# STM32F05.net
KiCad netlist of a schematic drawn in EAGLE
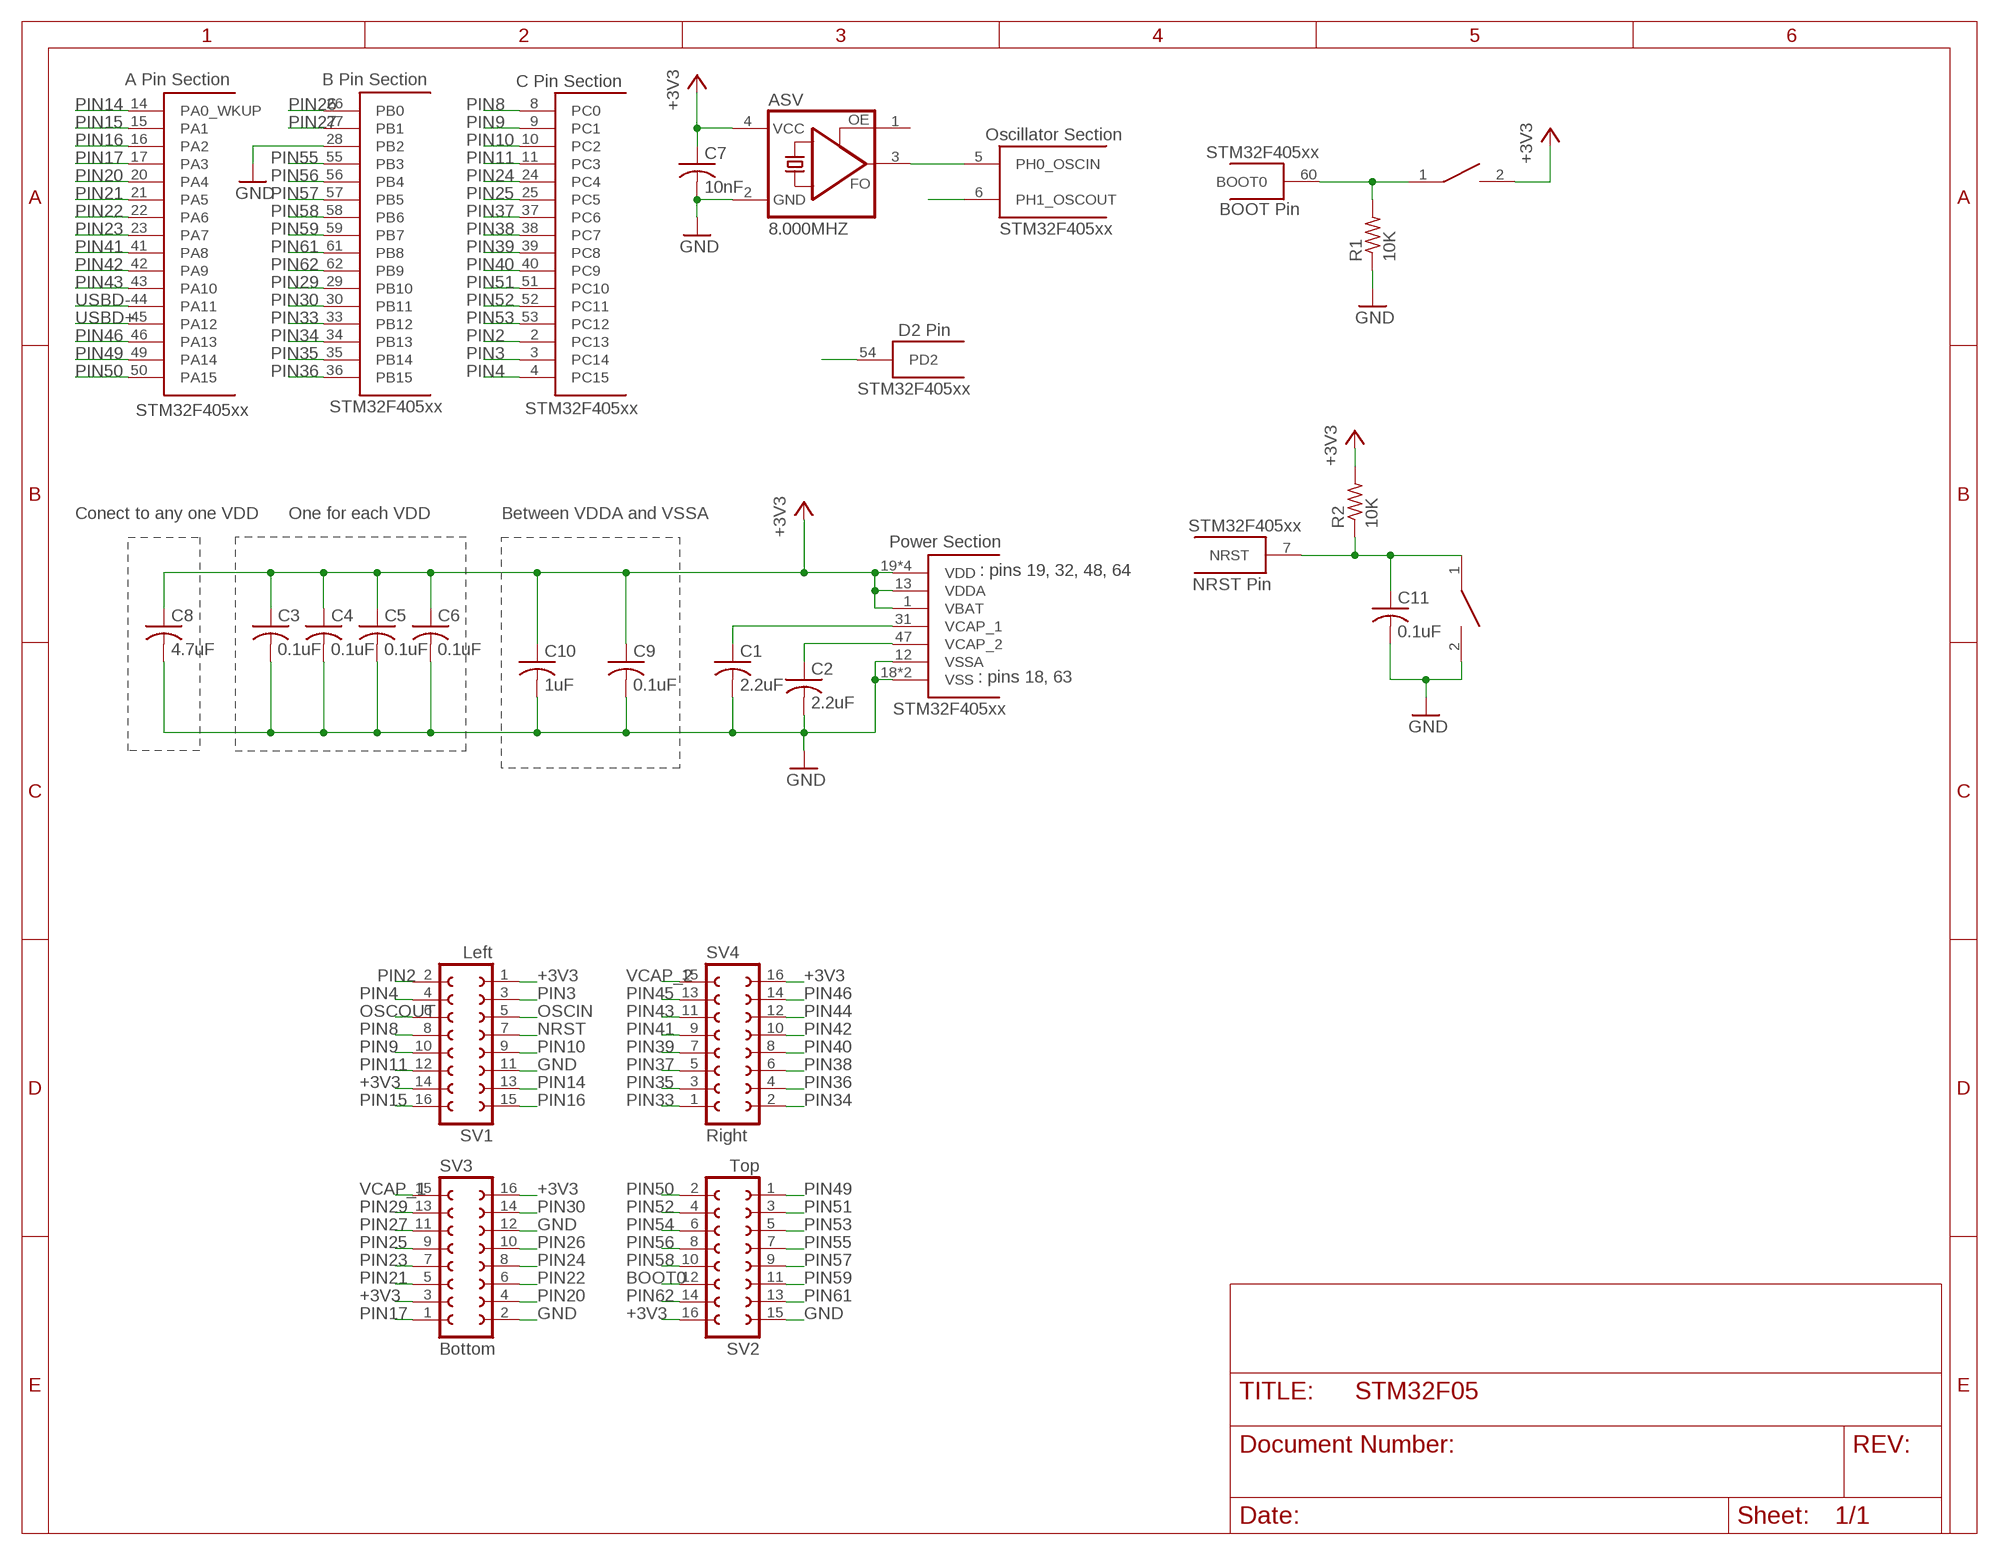
[diagram p0: schematic, sheet 1, part 1 of 2]
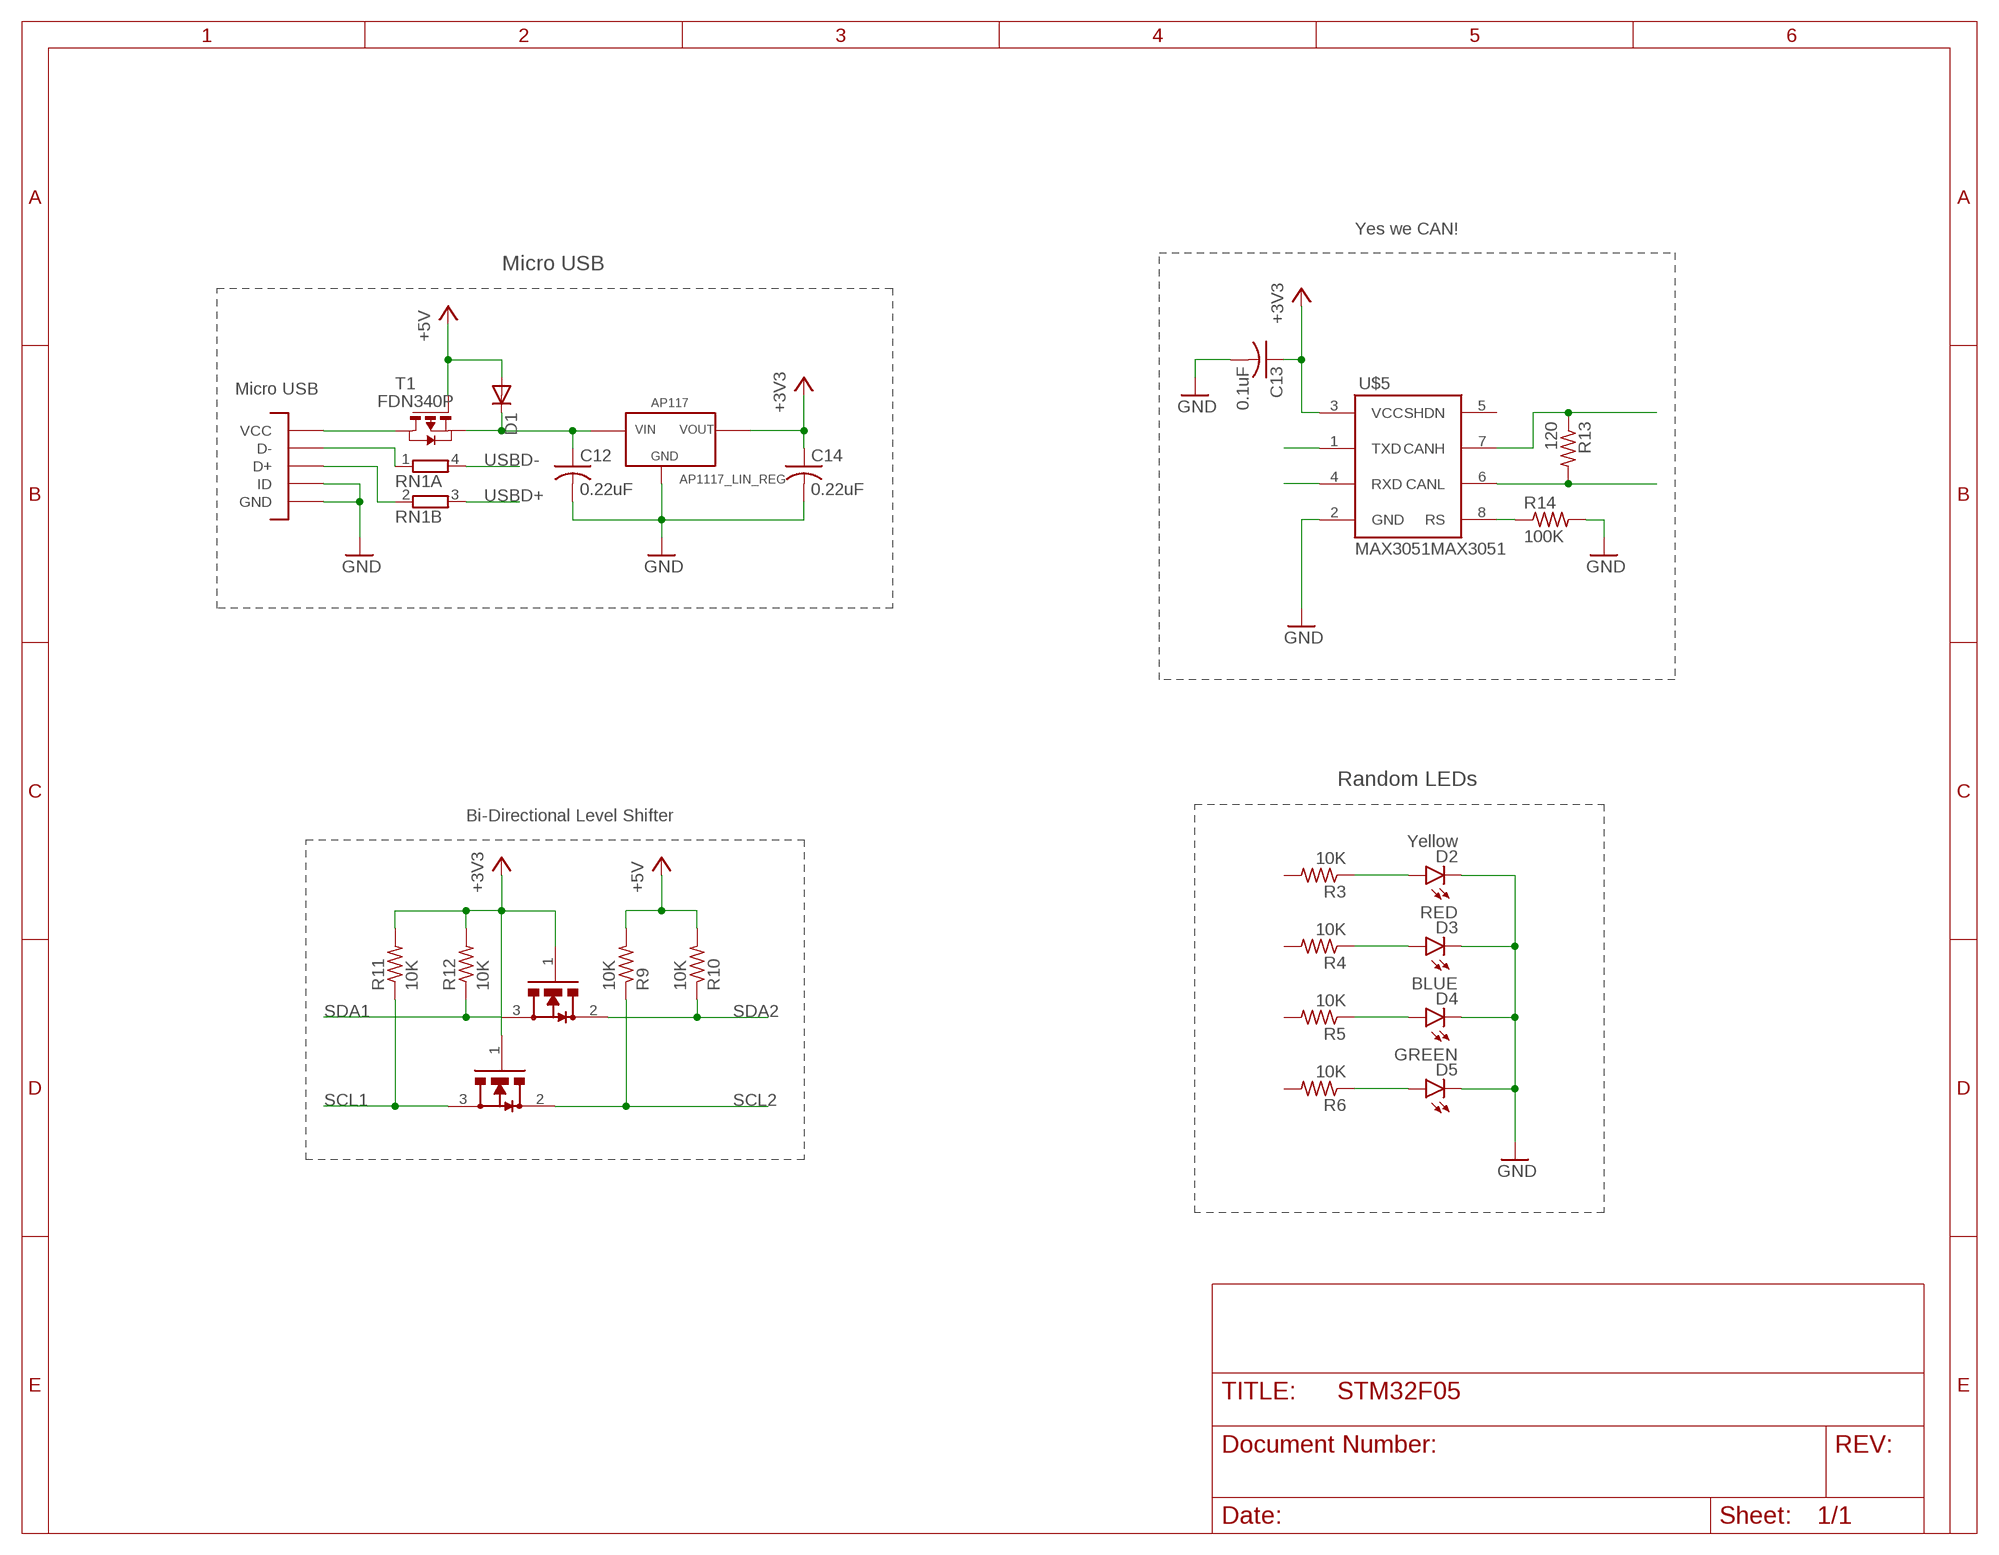
[diagram p1: schematic, sheet 1, part 2 of 2]

(export (version "E")
  (design (tool "Eeschema 10.0.6"))
  (components
    (comp (ref "ASV")
      (value "8.000MHZ")
      (footprint "eagle-import:ASF")
      (libsource (lib "eagle-import") (part "ASF"))
    )
    (comp (ref "BSS138")
      (value "n-chanel mosfet")
      (footprint "eagle-import:SOT-23-BSS138")
      (libsource (lib "eagle-import") (part "BSS138"))
    )
    (comp (ref "C1")
      (value "2.2uF")
      (footprint "eagle-import:C0603")
      (libsource (lib "eagle-import") (part "C-USC0603"))
    )
    (comp (ref "C2")
      (value "2.2uF")
      (footprint "eagle-import:C0603")
      (libsource (lib "eagle-import") (part "C-USC0603"))
    )
    (comp (ref "C3")
      (value "0.1uF")
      (footprint "eagle-import:C0603")
      (libsource (lib "eagle-import") (part "C-USC0603"))
    )
    (comp (ref "C4")
      (value "0.1uF")
      (footprint "eagle-import:C0603")
      (libsource (lib "eagle-import") (part "C-USC0603"))
    )
    (comp (ref "C5")
      (value "0.1uF")
      (footprint "eagle-import:C0603")
      (libsource (lib "eagle-import") (part "C-USC0603"))
    )
    (comp (ref "C6")
      (value "0.1uF")
      (footprint "eagle-import:C0603")
      (libsource (lib "eagle-import") (part "C-USC0603"))
    )
    (comp (ref "C7")
      (value "10nF")
      (footprint "eagle-import:C0603")
      (libsource (lib "eagle-import") (part "C-USC0603"))
    )
    (comp (ref "C8")
      (value "4.7uF")
      (footprint "eagle-import:C0603")
      (libsource (lib "eagle-import") (part "C-USC0603"))
    )
    (comp (ref "C9")
      (value "0.1uF")
      (footprint "eagle-import:C0603")
      (libsource (lib "eagle-import") (part "C-USC0603"))
    )
    (comp (ref "C10")
      (value "1uF")
      (footprint "eagle-import:C0603")
      (libsource (lib "eagle-import") (part "C-USC0603"))
    )
    (comp (ref "C11")
      (value "0.1uF")
      (footprint "eagle-import:C0603")
      (libsource (lib "eagle-import") (part "C-USC0603"))
    )
    (comp (ref "C12")
      (value "0.22uF")
      (footprint "eagle-import:C0603")
      (libsource (lib "eagle-import") (part "C-USC0603"))
    )
    (comp (ref "C13")
      (value "0.1uF")
      (footprint "eagle-import:C0603")
      (libsource (lib "eagle-import") (part "C-USC0603"))
    )
    (comp (ref "C14")
      (value "0.22uF")
      (footprint "eagle-import:C0603")
      (libsource (lib "eagle-import") (part "C-USC0603"))
    )
    (comp (ref "D1")
      (value "DIODE-DO-214AC")
      (footprint "eagle-import:DO-214AC")
      (libsource (lib "eagle-import") (part "DIODE-DO-214AC"))
    )
    (comp (ref "D2")
      (value "Yellow")
      (footprint "eagle-import:LED-0603")
      (libsource (lib "eagle-import") (part "LED-YELLOW0603"))
    )
    (comp (ref "D3")
      (value "RED")
      (footprint "eagle-import:LED-0603")
      (libsource (lib "eagle-import") (part "LED-RED0603"))
    )
    (comp (ref "D4")
      (value "BLUE")
      (footprint "eagle-import:LED-0603")
      (libsource (lib "eagle-import") (part "LED-BLUE0603"))
    )
    (comp (ref "D5")
      (value "GREEN")
      (footprint "eagle-import:LED-0603")
      (libsource (lib "eagle-import") (part "LED-GREEN0603"))
    )
    (comp (ref "R1")
      (value "10K")
      (footprint "eagle-import:R0603")
      (libsource (lib "eagle-import") (part "R-US_R0603"))
    )
    (comp (ref "R2")
      (value "10K")
      (footprint "eagle-import:R0603")
      (libsource (lib "eagle-import") (part "R-US_R0603"))
    )
    (comp (ref "R3")
      (value "10K")
      (footprint "eagle-import:R0603")
      (libsource (lib "eagle-import") (part "R-US_R0603"))
    )
    (comp (ref "R4")
      (value "10K")
      (footprint "eagle-import:R0603")
      (libsource (lib "eagle-import") (part "R-US_R0603"))
    )
    (comp (ref "R5")
      (value "10K")
      (footprint "eagle-import:R0603")
      (libsource (lib "eagle-import") (part "R-US_R0603"))
    )
    (comp (ref "R6")
      (value "10K")
      (footprint "eagle-import:R0603")
      (libsource (lib "eagle-import") (part "R-US_R0603"))
    )
    (comp (ref "R9")
      (value "10K")
      (footprint "eagle-import:R0603")
      (libsource (lib "eagle-import") (part "R-US_R0603"))
    )
    (comp (ref "R10")
      (value "10K")
      (footprint "eagle-import:R0603")
      (libsource (lib "eagle-import") (part "R-US_R0603"))
    )
    (comp (ref "R11")
      (value "10K")
      (footprint "eagle-import:R0603")
      (libsource (lib "eagle-import") (part "R-US_R0603"))
    )
    (comp (ref "R12")
      (value "10K")
      (footprint "eagle-import:R0603")
      (libsource (lib "eagle-import") (part "R-US_R0603"))
    )
    (comp (ref "R13")
      (value "120")
      (footprint "eagle-import:R0603")
      (libsource (lib "eagle-import") (part "R-US_R0603"))
    )
    (comp (ref "R14")
      (value "100K")
      (footprint "eagle-import:R0603")
      (libsource (lib "eagle-import") (part "R-US_R0603"))
    )
    (comp (ref "RN1")
      (value "2R-NEXBV4V")
      (footprint "eagle-import:EXBV4V")
      (fields (field (name "MF") "Rohm Semiconductor") (field (name "MPN") "MNR12ERAPJ220"))
      (libsource (lib "eagle-import") (part "2R-NEXBV4V"))
    )
    (comp (ref "SV1")
      (value "Left")
      (footprint "eagle-import:FE08-2")
      (libsource (lib "eagle-import") (part "FE08-2"))
    )
    (comp (ref "SV2")
      (value "Top")
      (footprint "eagle-import:FE08-2")
      (libsource (lib "eagle-import") (part "FE08-2"))
    )
    (comp (ref "SV3")
      (value "Bottom")
      (footprint "eagle-import:FE08-2")
      (libsource (lib "eagle-import") (part "FE08-2"))
    )
    (comp (ref "SV4")
      (value "Right")
      (footprint "eagle-import:FE08-2")
      (libsource (lib "eagle-import") (part "FE08-2"))
    )
    (comp (ref "T1")
      (value "FDN340P")
      (footprint "eagle-import:SOT-23")
      (libsource (lib "eagle-import") (part "FDN340P"))
    )
    (comp (ref "T2")
      (value "AP1117_LIN_REG")
      (footprint "eagle-import:SOT223")
      (libsource (lib "eagle-import") (part "AP1117_LIN_REG"))
    )
    (comp (ref "U$1")
      (value "STM32F405")
      (footprint "eagle-import:LQFP64")
      (libsource (lib "eagle-import") (part "STM32F405"))
    )
    (comp (ref "U$2")
      (value "SWITCH")
      (footprint "eagle-import:SW_2512")
      (libsource (lib "eagle-import") (part "SWITCH"))
    )
    (comp (ref "U$3")
      (value "SWITCH")
      (footprint "eagle-import:SW_2512")
      (libsource (lib "eagle-import") (part "SWITCH"))
    )
    (comp (ref "U$4")
      (value "MICROUSB")
      (footprint "eagle-import:MICRO_B")
      (libsource (lib "eagle-import") (part "MICROUSB"))
    )
    (comp (ref "U$5")
      (value "MAX3051MAX3051")
      (footprint "eagle-import:SOT23-8L")
      (libsource (lib "eagle-import") (part "MAX3051MAX3051"))
    )
    (comp (ref "U$6")
      (value "BSS138")
      (footprint "eagle-import:SOT-23-BSS138")
      (libsource (lib "eagle-import") (part "BSS138"))
    )
  )
  (nets
    (net (code "1") (name "+3V3") (class "Default")
      (node (ref "ASV") (pin "4") (pinfunction "VCC_4") (pintype "power_in"))
      (node (ref "BSS138") (pin "1") (pinfunction "G_1") (pintype "bidirectional"))
      (node (ref "C10") (pin "1") (pinfunction "1_1") (pintype "passive"))
      (node (ref "C13") (pin "1") (pinfunction "1_1") (pintype "passive"))
      (node (ref "C14") (pin "1") (pinfunction "1_1") (pintype "passive"))
      (node (ref "C3") (pin "1") (pinfunction "1_1") (pintype "passive"))
      (node (ref "C4") (pin "1") (pinfunction "1_1") (pintype "passive"))
      (node (ref "C5") (pin "1") (pinfunction "1_1") (pintype "passive"))
      (node (ref "C6") (pin "1") (pinfunction "1_1") (pintype "passive"))
      (node (ref "C7") (pin "1") (pinfunction "1_1") (pintype "passive"))
      (node (ref "C8") (pin "1") (pinfunction "1_1") (pintype "passive"))
      (node (ref "C9") (pin "1") (pinfunction "1_1") (pintype "passive"))
      (node (ref "R11") (pin "2") (pinfunction "2_2") (pintype "passive"))
      (node (ref "R12") (pin "2") (pinfunction "2_2") (pintype "passive"))
      (node (ref "R2") (pin "2") (pinfunction "2_2") (pintype "passive"))
      (node (ref "SV1") (pin "1") (pinfunction "1_1") (pintype "passive"))
      (node (ref "SV1") (pin "14") (pinfunction "14_14") (pintype "passive"))
      (node (ref "SV2") (pin "16") (pinfunction "16_16") (pintype "passive"))
      (node (ref "SV3") (pin "16") (pinfunction "16_16") (pintype "passive"))
      (node (ref "SV3") (pin "3") (pinfunction "3_3") (pintype "passive"))
      (node (ref "SV4") (pin "16") (pinfunction "16_16") (pintype "passive"))
      (node (ref "T2") (pin "TAB") (pinfunction "VOUT_TAB") (pintype "output"))
      (node (ref "T2") (pin "VOUT") (pinfunction "VOUT_VOUT") (pintype "output"))
      (node (ref "U$1") (pin "1") (pinfunction "VBAT_1") (pintype "bidirectional"))
      (node (ref "U$1") (pin "13") (pinfunction "VDDA_13") (pintype "bidirectional"))
      (node (ref "U$1") (pin "19") (pinfunction "VDD_19") (pintype "bidirectional"))
      (node (ref "U$1") (pin "32") (pinfunction "VDD_32") (pintype "bidirectional"))
      (node (ref "U$1") (pin "48") (pinfunction "VDD_48") (pintype "bidirectional"))
      (node (ref "U$1") (pin "64") (pinfunction "VDD_64") (pintype "bidirectional"))
      (node (ref "U$2") (pin "2") (pinfunction "P$2_2") (pintype "bidirectional"))
      (node (ref "U$5") (pin "3") (pinfunction "VCC_3") (pintype "bidirectional"))
      (node (ref "U$6") (pin "1") (pinfunction "G_1") (pintype "bidirectional"))
    )
    (net (code "2") (name "+5V") (class "Default")
      (node (ref "D1") (pin "A") (pinfunction "A_A") (pintype "passive"))
      (node (ref "R10") (pin "2") (pinfunction "2_2") (pintype "passive"))
      (node (ref "R9") (pin "2") (pinfunction "2_2") (pintype "passive"))
      (node (ref "T1") (pin "3") (pinfunction "G_3") (pintype "passive"))
    )
    (net (code "3") (name "/BOOT0") (class "Default")
      (node (ref "R1") (pin "2") (pinfunction "2_2") (pintype "passive"))
      (node (ref "SV2") (pin "12") (pinfunction "12_12") (pintype "passive"))
      (node (ref "U$1") (pin "60") (pinfunction "BOOT0_60") (pintype "bidirectional"))
      (node (ref "U$2") (pin "1") (pinfunction "P$1_1") (pintype "bidirectional"))
    )
    (net (code "4") (name "/NRST") (class "Default")
      (node (ref "C11") (pin "1") (pinfunction "1_1") (pintype "passive"))
      (node (ref "R2") (pin "1") (pinfunction "1_1") (pintype "passive"))
      (node (ref "SV1") (pin "7") (pinfunction "7_7") (pintype "passive"))
      (node (ref "U$1") (pin "7") (pinfunction "NRST_7") (pintype "bidirectional"))
      (node (ref "U$3") (pin "1") (pinfunction "P$1_1") (pintype "bidirectional"))
    )
    (net (code "5") (name "/OSCIN") (class "Default")
      (node (ref "ASV") (pin "3") (pinfunction "FO_3") (pintype "output"))
      (node (ref "SV1") (pin "5") (pinfunction "5_5") (pintype "passive"))
      (node (ref "U$1") (pin "5") (pinfunction "PH0_OSCIN_5") (pintype "bidirectional"))
    )
    (net (code "6") (name "/OSCOUT") (class "Default")
      (node (ref "SV1") (pin "6") (pinfunction "6_6") (pintype "passive"))
      (node (ref "U$1") (pin "6") (pinfunction "PH1_OSCOUT_6") (pintype "bidirectional"))
    )
    (net (code "7") (name "/PIN2") (class "Default")
      (node (ref "SV1") (pin "2") (pinfunction "2_2") (pintype "passive"))
      (node (ref "U$1") (pin "2") (pinfunction "PC13_2") (pintype "bidirectional"))
    )
    (net (code "8") (name "/PIN3") (class "Default")
      (node (ref "SV1") (pin "3") (pinfunction "3_3") (pintype "passive"))
      (node (ref "U$1") (pin "3") (pinfunction "PC14_3") (pintype "bidirectional"))
    )
    (net (code "9") (name "/PIN4") (class "Default")
      (node (ref "SV1") (pin "4") (pinfunction "4_4") (pintype "passive"))
      (node (ref "U$1") (pin "4") (pinfunction "PC15_4") (pintype "bidirectional"))
    )
    (net (code "10") (name "/PIN8") (class "Default")
      (node (ref "SV1") (pin "8") (pinfunction "8_8") (pintype "passive"))
      (node (ref "U$1") (pin "8") (pinfunction "PC0_8") (pintype "bidirectional"))
    )
    (net (code "11") (name "/PIN9") (class "Default")
      (node (ref "SV1") (pin "10") (pinfunction "10_10") (pintype "passive"))
      (node (ref "U$1") (pin "9") (pinfunction "PC1_9") (pintype "bidirectional"))
    )
    (net (code "12") (name "/PIN10") (class "Default")
      (node (ref "SV1") (pin "9") (pinfunction "9_9") (pintype "passive"))
      (node (ref "U$1") (pin "10") (pinfunction "PC2_10") (pintype "bidirectional"))
    )
    (net (code "13") (name "/PIN11") (class "Default")
      (node (ref "SV1") (pin "12") (pinfunction "12_12") (pintype "passive"))
      (node (ref "U$1") (pin "11") (pinfunction "PC3_11") (pintype "bidirectional"))
    )
    (net (code "14") (name "/PIN14") (class "Default")
      (node (ref "SV1") (pin "13") (pinfunction "13_13") (pintype "passive"))
      (node (ref "U$1") (pin "14") (pinfunction "PA0_WKUP_14") (pintype "bidirectional"))
    )
    (net (code "15") (name "/PIN15") (class "Default")
      (node (ref "SV1") (pin "16") (pinfunction "16_16") (pintype "passive"))
      (node (ref "U$1") (pin "15") (pinfunction "PA1_15") (pintype "bidirectional"))
    )
    (net (code "16") (name "/PIN16") (class "Default")
      (node (ref "SV1") (pin "15") (pinfunction "15_15") (pintype "passive"))
      (node (ref "U$1") (pin "16") (pinfunction "PA2_16") (pintype "bidirectional"))
    )
    (net (code "17") (name "/PIN17") (class "Default")
      (node (ref "SV3") (pin "1") (pinfunction "1_1") (pintype "passive"))
      (node (ref "U$1") (pin "17") (pinfunction "PA3_17") (pintype "bidirectional"))
    )
    (net (code "18") (name "/PIN20") (class "Default")
      (node (ref "SV3") (pin "4") (pinfunction "4_4") (pintype "passive"))
      (node (ref "U$1") (pin "20") (pinfunction "PA4_20") (pintype "bidirectional"))
    )
    (net (code "19") (name "/PIN21") (class "Default")
      (node (ref "SV3") (pin "5") (pinfunction "5_5") (pintype "passive"))
      (node (ref "U$1") (pin "21") (pinfunction "PA5_21") (pintype "bidirectional"))
    )
    (net (code "20") (name "/PIN22") (class "Default")
      (node (ref "SV3") (pin "6") (pinfunction "6_6") (pintype "passive"))
      (node (ref "U$1") (pin "22") (pinfunction "PA6_22") (pintype "bidirectional"))
    )
    (net (code "21") (name "/PIN23") (class "Default")
      (node (ref "SV3") (pin "7") (pinfunction "7_7") (pintype "passive"))
      (node (ref "U$1") (pin "23") (pinfunction "PA7_23") (pintype "bidirectional"))
    )
    (net (code "22") (name "/PIN24") (class "Default")
      (node (ref "SV3") (pin "8") (pinfunction "8_8") (pintype "passive"))
      (node (ref "U$1") (pin "24") (pinfunction "PC4_24") (pintype "bidirectional"))
    )
    (net (code "23") (name "/PIN25") (class "Default")
      (node (ref "SV3") (pin "9") (pinfunction "9_9") (pintype "passive"))
      (node (ref "U$1") (pin "25") (pinfunction "PC5_25") (pintype "bidirectional"))
    )
    (net (code "24") (name "/PIN26") (class "Default")
      (node (ref "SV3") (pin "10") (pinfunction "10_10") (pintype "passive"))
      (node (ref "U$1") (pin "26") (pinfunction "PB0_26") (pintype "bidirectional"))
    )
    (net (code "25") (name "/PIN27") (class "Default")
      (node (ref "SV3") (pin "11") (pinfunction "11_11") (pintype "passive"))
      (node (ref "U$1") (pin "27") (pinfunction "PB1_27") (pintype "bidirectional"))
    )
    (net (code "26") (name "/PIN29") (class "Default")
      (node (ref "SV3") (pin "13") (pinfunction "13_13") (pintype "passive"))
      (node (ref "U$1") (pin "29") (pinfunction "PB10_29") (pintype "bidirectional"))
    )
    (net (code "27") (name "/PIN30") (class "Default")
      (node (ref "SV3") (pin "14") (pinfunction "14_14") (pintype "passive"))
      (node (ref "U$1") (pin "30") (pinfunction "PB11_30") (pintype "bidirectional"))
    )
    (net (code "28") (name "/PIN33") (class "Default")
      (node (ref "SV4") (pin "1") (pinfunction "1_1") (pintype "passive"))
      (node (ref "U$1") (pin "33") (pinfunction "PB12_33") (pintype "bidirectional"))
    )
    (net (code "29") (name "/PIN34") (class "Default")
      (node (ref "SV4") (pin "2") (pinfunction "2_2") (pintype "passive"))
      (node (ref "U$1") (pin "34") (pinfunction "PB13_34") (pintype "bidirectional"))
    )
    (net (code "30") (name "/PIN35") (class "Default")
      (node (ref "SV4") (pin "3") (pinfunction "3_3") (pintype "passive"))
      (node (ref "U$1") (pin "35") (pinfunction "PB14_35") (pintype "bidirectional"))
    )
    (net (code "31") (name "/PIN36") (class "Default")
      (node (ref "SV4") (pin "4") (pinfunction "4_4") (pintype "passive"))
      (node (ref "U$1") (pin "36") (pinfunction "PB15_36") (pintype "bidirectional"))
    )
    (net (code "32") (name "/PIN37") (class "Default")
      (node (ref "SV4") (pin "5") (pinfunction "5_5") (pintype "passive"))
      (node (ref "U$1") (pin "37") (pinfunction "PC6_37") (pintype "bidirectional"))
    )
    (net (code "33") (name "/PIN38") (class "Default")
      (node (ref "SV4") (pin "6") (pinfunction "6_6") (pintype "passive"))
      (node (ref "U$1") (pin "38") (pinfunction "PC7_38") (pintype "bidirectional"))
    )
    (net (code "34") (name "/PIN39") (class "Default")
      (node (ref "SV4") (pin "7") (pinfunction "7_7") (pintype "passive"))
      (node (ref "U$1") (pin "39") (pinfunction "PC8_39") (pintype "bidirectional"))
    )
    (net (code "35") (name "/PIN40") (class "Default")
      (node (ref "SV4") (pin "8") (pinfunction "8_8") (pintype "passive"))
      (node (ref "U$1") (pin "40") (pinfunction "PC9_40") (pintype "bidirectional"))
    )
    (net (code "36") (name "/PIN41") (class "Default")
      (node (ref "SV4") (pin "9") (pinfunction "9_9") (pintype "passive"))
      (node (ref "U$1") (pin "41") (pinfunction "PA8_41") (pintype "bidirectional"))
    )
    (net (code "37") (name "/PIN42") (class "Default")
      (node (ref "SV4") (pin "10") (pinfunction "10_10") (pintype "passive"))
      (node (ref "U$1") (pin "42") (pinfunction "PA9_42") (pintype "bidirectional"))
    )
    (net (code "38") (name "/PIN43") (class "Default")
      (node (ref "SV4") (pin "11") (pinfunction "11_11") (pintype "passive"))
      (node (ref "U$1") (pin "43") (pinfunction "PA10_43") (pintype "bidirectional"))
    )
    (net (code "39") (name "/PIN44") (class "Default")
      (node (ref "SV4") (pin "12") (pinfunction "12_12") (pintype "passive"))
    )
    (net (code "40") (name "/PIN45") (class "Default")
      (node (ref "SV4") (pin "13") (pinfunction "13_13") (pintype "passive"))
    )
    (net (code "41") (name "/PIN46") (class "Default")
      (node (ref "SV4") (pin "14") (pinfunction "14_14") (pintype "passive"))
      (node (ref "U$1") (pin "46") (pinfunction "PA13_46") (pintype "bidirectional"))
    )
    (net (code "42") (name "/PIN49") (class "Default")
      (node (ref "SV2") (pin "1") (pinfunction "1_1") (pintype "passive"))
      (node (ref "U$1") (pin "49") (pinfunction "PA14_49") (pintype "bidirectional"))
    )
    (net (code "43") (name "/PIN50") (class "Default")
      (node (ref "SV2") (pin "2") (pinfunction "2_2") (pintype "passive"))
      (node (ref "U$1") (pin "50") (pinfunction "PA15_50") (pintype "bidirectional"))
    )
    (net (code "44") (name "/PIN51") (class "Default")
      (node (ref "SV2") (pin "3") (pinfunction "3_3") (pintype "passive"))
      (node (ref "U$1") (pin "51") (pinfunction "PC10_51") (pintype "bidirectional"))
    )
    (net (code "45") (name "/PIN52") (class "Default")
      (node (ref "SV2") (pin "4") (pinfunction "4_4") (pintype "passive"))
      (node (ref "U$1") (pin "52") (pinfunction "PC11_52") (pintype "bidirectional"))
    )
    (net (code "46") (name "/PIN53") (class "Default")
      (node (ref "SV2") (pin "5") (pinfunction "5_5") (pintype "passive"))
      (node (ref "U$1") (pin "53") (pinfunction "PC12_53") (pintype "bidirectional"))
    )
    (net (code "47") (name "/PIN54") (class "Default")
      (node (ref "SV2") (pin "6") (pinfunction "6_6") (pintype "passive"))
      (node (ref "U$1") (pin "54") (pinfunction "PD2_54") (pintype "bidirectional"))
    )
    (net (code "48") (name "/PIN55") (class "Default")
      (node (ref "SV2") (pin "7") (pinfunction "7_7") (pintype "passive"))
      (node (ref "U$1") (pin "55") (pinfunction "PB3_55") (pintype "bidirectional"))
    )
    (net (code "49") (name "/PIN56") (class "Default")
      (node (ref "SV2") (pin "8") (pinfunction "8_8") (pintype "passive"))
      (node (ref "U$1") (pin "56") (pinfunction "PB4_56") (pintype "bidirectional"))
    )
    (net (code "50") (name "/PIN57") (class "Default")
      (node (ref "SV2") (pin "9") (pinfunction "9_9") (pintype "passive"))
      (node (ref "U$1") (pin "57") (pinfunction "PB5_57") (pintype "bidirectional"))
    )
    (net (code "51") (name "/PIN58") (class "Default")
      (node (ref "SV2") (pin "10") (pinfunction "10_10") (pintype "passive"))
      (node (ref "U$1") (pin "58") (pinfunction "PB6_58") (pintype "bidirectional"))
    )
    (net (code "52") (name "/PIN59") (class "Default")
      (node (ref "SV2") (pin "11") (pinfunction "11_11") (pintype "passive"))
      (node (ref "U$1") (pin "59") (pinfunction "PB7_59") (pintype "bidirectional"))
    )
    (net (code "53") (name "/PIN61") (class "Default")
      (node (ref "SV2") (pin "13") (pinfunction "13_13") (pintype "passive"))
      (node (ref "U$1") (pin "61") (pinfunction "PB8_61") (pintype "bidirectional"))
    )
    (net (code "54") (name "/PIN62") (class "Default")
      (node (ref "SV2") (pin "14") (pinfunction "14_14") (pintype "passive"))
      (node (ref "U$1") (pin "62") (pinfunction "PB9_62") (pintype "bidirectional"))
    )
    (net (code "55") (name "/SCL1") (class "Default")
      (node (ref "BSS138") (pin "3") (pinfunction "S_3") (pintype "bidirectional"))
      (node (ref "R11") (pin "1") (pinfunction "1_1") (pintype "passive"))
    )
    (net (code "56") (name "/SCL2") (class "Default")
      (node (ref "BSS138") (pin "2") (pinfunction "D_2") (pintype "bidirectional"))
      (node (ref "R9") (pin "1") (pinfunction "1_1") (pintype "passive"))
    )
    (net (code "57") (name "/SDA1") (class "Default")
      (node (ref "R12") (pin "1") (pinfunction "1_1") (pintype "passive"))
      (node (ref "U$6") (pin "3") (pinfunction "S_3") (pintype "bidirectional"))
    )
    (net (code "58") (name "/SDA2") (class "Default")
      (node (ref "R10") (pin "1") (pinfunction "1_1") (pintype "passive"))
      (node (ref "U$6") (pin "2") (pinfunction "D_2") (pintype "bidirectional"))
    )
    (net (code "59") (name "/USBD+") (class "Default")
      (node (ref "RN1") (pin "3") (pinfunction "2_3") (pintype "passive"))
      (node (ref "U$1") (pin "45") (pinfunction "PA12_45") (pintype "bidirectional"))
    )
    (net (code "60") (name "/USBD-") (class "Default")
      (node (ref "RN1") (pin "4") (pinfunction "2_4") (pintype "passive"))
      (node (ref "U$1") (pin "44") (pinfunction "PA11_44") (pintype "bidirectional"))
    )
    (net (code "61") (name "/VCAP_1") (class "Default")
      (node (ref "C1") (pin "1") (pinfunction "1_1") (pintype "passive"))
      (node (ref "SV3") (pin "15") (pinfunction "15_15") (pintype "passive"))
      (node (ref "U$1") (pin "31") (pinfunction "VCAP_1_31") (pintype "bidirectional"))
    )
    (net (code "62") (name "/VCAP_2") (class "Default")
      (node (ref "C2") (pin "1") (pinfunction "1_1") (pintype "passive"))
      (node (ref "SV4") (pin "15") (pinfunction "15_15") (pintype "passive"))
      (node (ref "U$1") (pin "47") (pinfunction "VCAP_2_47") (pintype "bidirectional"))
    )
    (net (code "63") (name "GND") (class "Default")
      (node (ref "ASV") (pin "2") (pinfunction "GND_2") (pintype "power_in"))
      (node (ref "C1") (pin "2") (pinfunction "2_2") (pintype "passive"))
      (node (ref "C10") (pin "2") (pinfunction "2_2") (pintype "passive"))
      (node (ref "C11") (pin "2") (pinfunction "2_2") (pintype "passive"))
      (node (ref "C12") (pin "2") (pinfunction "2_2") (pintype "passive"))
      (node (ref "C13") (pin "2") (pinfunction "2_2") (pintype "passive"))
      (node (ref "C14") (pin "2") (pinfunction "2_2") (pintype "passive"))
      (node (ref "C2") (pin "2") (pinfunction "2_2") (pintype "passive"))
      (node (ref "C3") (pin "2") (pinfunction "2_2") (pintype "passive"))
      (node (ref "C4") (pin "2") (pinfunction "2_2") (pintype "passive"))
      (node (ref "C5") (pin "2") (pinfunction "2_2") (pintype "passive"))
      (node (ref "C6") (pin "2") (pinfunction "2_2") (pintype "passive"))
      (node (ref "C7") (pin "2") (pinfunction "2_2") (pintype "passive"))
      (node (ref "C8") (pin "2") (pinfunction "2_2") (pintype "passive"))
      (node (ref "C9") (pin "2") (pinfunction "2_2") (pintype "passive"))
      (node (ref "D2") (pin "C") (pinfunction "C_C") (pintype "passive"))
      (node (ref "D3") (pin "C") (pinfunction "C_C") (pintype "passive"))
      (node (ref "D4") (pin "C") (pinfunction "C_C") (pintype "passive"))
      (node (ref "D5") (pin "C") (pinfunction "C_C") (pintype "passive"))
      (node (ref "R1") (pin "1") (pinfunction "1_1") (pintype "passive"))
      (node (ref "R14") (pin "2") (pinfunction "2_2") (pintype "passive"))
      (node (ref "SV1") (pin "11") (pinfunction "11_11") (pintype "passive"))
      (node (ref "SV2") (pin "15") (pinfunction "15_15") (pintype "passive"))
      (node (ref "SV3") (pin "12") (pinfunction "12_12") (pintype "passive"))
      (node (ref "SV3") (pin "2") (pinfunction "2_2") (pintype "passive"))
      (node (ref "T2") (pin "GND") (pinfunction "GND_GND") (pintype "bidirectional"))
      (node (ref "U$1") (pin "12") (pinfunction "VSSA_12") (pintype "bidirectional"))
      (node (ref "U$1") (pin "18") (pinfunction "VSS_18") (pintype "bidirectional"))
      (node (ref "U$1") (pin "28") (pinfunction "PB2_28") (pintype "bidirectional"))
      (node (ref "U$1") (pin "63") (pinfunction "VSS_63") (pintype "bidirectional"))
      (node (ref "U$3") (pin "2") (pinfunction "P$2_2") (pintype "bidirectional"))
      (node (ref "U$4") (pin "GND1") (pinfunction "GND_GND1") (pintype "bidirectional"))
      (node (ref "U$4") (pin "GND2") (pinfunction "GND_GND2") (pintype "bidirectional"))
      (node (ref "U$4") (pin "GND3") (pinfunction "GND_GND3") (pintype "bidirectional"))
      (node (ref "U$4") (pin "GND4") (pinfunction "GND_GND4") (pintype "bidirectional"))
      (node (ref "U$4") (pin "GND7") (pinfunction "GND_GND7") (pintype "bidirectional"))
      (node (ref "U$4") (pin "GND8") (pinfunction "GND_GND8") (pintype "bidirectional"))
      (node (ref "U$4") (pin "P4") (pinfunction "ID_P4") (pintype "bidirectional"))
      (node (ref "U$4") (pin "P5") (pinfunction "GND_P5") (pintype "bidirectional"))
      (node (ref "U$5") (pin "2") (pinfunction "GND_2") (pintype "bidirectional"))
    )
    (net (code "64") (name "Net-(D2-PadA)") (class "Default")
      (node (ref "D2") (pin "A") (pinfunction "A_A") (pintype "passive"))
      (node (ref "R3") (pin "1") (pinfunction "1_1") (pintype "passive"))
    )
    (net (code "65") (name "Net-(D3-PadA)") (class "Default")
      (node (ref "D3") (pin "A") (pinfunction "A_A") (pintype "passive"))
      (node (ref "R4") (pin "1") (pinfunction "1_1") (pintype "passive"))
    )
    (net (code "66") (name "Net-(D4-PadA)") (class "Default")
      (node (ref "D4") (pin "A") (pinfunction "A_A") (pintype "passive"))
      (node (ref "R5") (pin "1") (pinfunction "1_1") (pintype "passive"))
    )
    (net (code "67") (name "Net-(D5-PadA)") (class "Default")
      (node (ref "D5") (pin "A") (pinfunction "A_A") (pintype "passive"))
      (node (ref "R6") (pin "1") (pinfunction "1_1") (pintype "passive"))
    )
    (net (code "68") (name "Net-(RN1B-1)") (class "Default")
      (node (ref "RN1") (pin "2") (pinfunction "1_2") (pintype "passive"))
      (node (ref "U$4") (pin "P3") (pinfunction "D+_P3") (pintype "bidirectional"))
    )
    (net (code "69") (name "Net-(T1-D)") (class "Default")
      (node (ref "T1") (pin "1") (pinfunction "D_1") (pintype "passive"))
      (node (ref "U$4") (pin "P1") (pinfunction "VCC_P1") (pintype "bidirectional"))
    )
    (net (code "70") (name "Net-(T1-S)") (class "Default")
      (node (ref "C12") (pin "1") (pinfunction "1_1") (pintype "passive"))
      (node (ref "D1") (pin "C") (pinfunction "C_C") (pintype "passive"))
      (node (ref "T1") (pin "2") (pinfunction "S_2") (pintype "passive"))
      (node (ref "T2") (pin "VIN") (pinfunction "VIN_VIN") (pintype "input"))
    )
    (net (code "71") (name "Net-(U$4-D-)") (class "Default")
      (node (ref "RN1") (pin "1") (pinfunction "1_1") (pintype "passive"))
      (node (ref "U$4") (pin "P2") (pinfunction "D-_P2") (pintype "bidirectional"))
    )
    (net (code "72") (name "Net-(U$5-CANH)") (class "Default")
      (node (ref "R13") (pin "1") (pinfunction "1_1") (pintype "passive"))
      (node (ref "U$5") (pin "7") (pinfunction "CANH_7") (pintype "bidirectional"))
    )
    (net (code "73") (name "Net-(U$5-CANL)") (class "Default")
      (node (ref "R13") (pin "2") (pinfunction "2_2") (pintype "passive"))
      (node (ref "U$5") (pin "6") (pinfunction "CANL_6") (pintype "bidirectional"))
    )
    (net (code "74") (name "Net-(U$5-RS)") (class "Default")
      (node (ref "R14") (pin "1") (pinfunction "1_1") (pintype "passive"))
      (node (ref "U$5") (pin "8") (pinfunction "RS_8") (pintype "bidirectional"))
    )
    (net (code "75") (name "unconnected-(ASV-OE-Pad1)") (class "Default")
      (node (ref "ASV") (pin "1") (pinfunction "OE_1") (pintype "input"))
    )
    (net (code "76") (name "unconnected-(R3-Pad2)") (class "Default")
      (node (ref "R3") (pin "2") (pinfunction "2_2") (pintype "passive"))
    )
    (net (code "77") (name "unconnected-(R4-Pad2)") (class "Default")
      (node (ref "R4") (pin "2") (pinfunction "2_2") (pintype "passive"))
    )
    (net (code "78") (name "unconnected-(R5-Pad2)") (class "Default")
      (node (ref "R5") (pin "2") (pinfunction "2_2") (pintype "passive"))
    )
    (net (code "79") (name "unconnected-(R6-Pad2)") (class "Default")
      (node (ref "R6") (pin "2") (pinfunction "2_2") (pintype "passive"))
    )
    (net (code "80") (name "unconnected-(U$5-RXD-Pad4)") (class "Default")
      (node (ref "U$5") (pin "4") (pinfunction "RXD_4") (pintype "bidirectional"))
    )
    (net (code "81") (name "unconnected-(U$5-SHDN-Pad5)") (class "Default")
      (node (ref "U$5") (pin "5") (pinfunction "SHDN_5") (pintype "bidirectional"))
    )
    (net (code "82") (name "unconnected-(U$5-TXD-Pad1)") (class "Default")
      (node (ref "U$5") (pin "1") (pinfunction "TXD_1") (pintype "bidirectional"))
    )
  )
)
